# 01_commref_config.net
KiCad netlist of a schematic drawn in Altium Designer
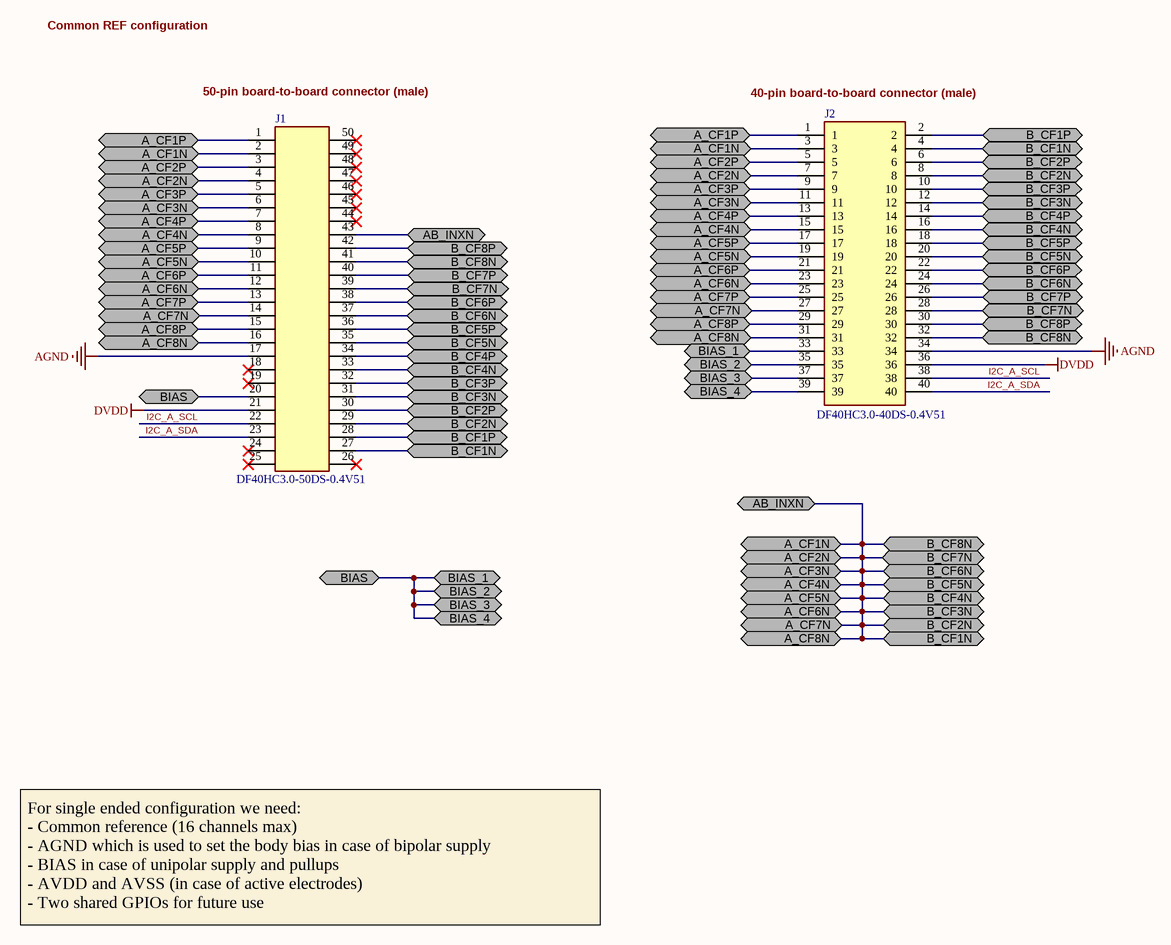
[diagram p0: 01_commref_config.SchDoc]

(export (version "E")
  (design (tool "Eeschema 10.0.6"))
  (components
    (comp (ref "J1")
      (value "DF40HC3.0-50DS-0.4V51")
      (footprint "CONN_DF40HC3.0-50DS-0.4V51_HIR")
      (description "No Description Available")
      (libsource (lib "DF40HC3P0-50DS-0P4V51") (part "DF40HC3.0-50DS-0.4V51"))
    )
    (comp (ref "J2")
      (value "DF40HC3.0-40DS-0.4V51")
      (footprint "CONN40_DF40HC-40DS_HIR")
      (description "No Description Available")
      (libsource (lib "DF40HC3P0-40DS-0P4V51") (part "DF40HC3.0-40DS-0.4V51"))
    )
  )
  (nets
    (net (code "1") (name "/AB_INXN") (class "Default")
      (node (ref "J1") (pin "10") (pintype "passive"))
      (node (ref "J1") (pin "12") (pintype "passive"))
      (node (ref "J1") (pin "14") (pintype "passive"))
      (node (ref "J1") (pin "16") (pintype "passive"))
      (node (ref "J1") (pin "2") (pintype "passive"))
      (node (ref "J1") (pin "27") (pintype "passive"))
      (node (ref "J1") (pin "29") (pintype "passive"))
      (node (ref "J1") (pin "31") (pintype "passive"))
      (node (ref "J1") (pin "33") (pintype "passive"))
      (node (ref "J1") (pin "35") (pintype "passive"))
      (node (ref "J1") (pin "37") (pintype "passive"))
      (node (ref "J1") (pin "39") (pintype "passive"))
      (node (ref "J1") (pin "4") (pintype "passive"))
      (node (ref "J1") (pin "41") (pintype "passive"))
      (node (ref "J1") (pin "43") (pintype "passive"))
      (node (ref "J1") (pin "6") (pintype "passive"))
      (node (ref "J1") (pin "8") (pintype "passive"))
      (node (ref "J2") (pin "11") (pinfunction "11_11") (pintype "passive"))
      (node (ref "J2") (pin "12") (pinfunction "12_12") (pintype "passive"))
      (node (ref "J2") (pin "15") (pinfunction "15_15") (pintype "passive"))
      (node (ref "J2") (pin "16") (pinfunction "16_16") (pintype "passive"))
      (node (ref "J2") (pin "19") (pinfunction "19_19") (pintype "passive"))
      (node (ref "J2") (pin "20") (pinfunction "20_20") (pintype "passive"))
      (node (ref "J2") (pin "23") (pinfunction "23_23") (pintype "passive"))
      (node (ref "J2") (pin "24") (pinfunction "24_24") (pintype "passive"))
      (node (ref "J2") (pin "27") (pinfunction "27_27") (pintype "passive"))
      (node (ref "J2") (pin "28") (pinfunction "28_28") (pintype "passive"))
      (node (ref "J2") (pin "3") (pinfunction "3_3") (pintype "passive"))
      (node (ref "J2") (pin "31") (pinfunction "31_31") (pintype "passive"))
      (node (ref "J2") (pin "32") (pinfunction "32_32") (pintype "passive"))
      (node (ref "J2") (pin "4") (pinfunction "4_4") (pintype "passive"))
      (node (ref "J2") (pin "7") (pinfunction "7_7") (pintype "passive"))
      (node (ref "J2") (pin "8") (pinfunction "8_8") (pintype "passive"))
    )
    (net (code "2") (name "/A_CF1P") (class "Default")
      (node (ref "J1") (pin "1") (pintype "passive"))
      (node (ref "J2") (pin "1") (pinfunction "1_1") (pintype "passive"))
    )
    (net (code "3") (name "/A_CF2P") (class "Default")
      (node (ref "J1") (pin "3") (pintype "passive"))
      (node (ref "J2") (pin "5") (pinfunction "5_5") (pintype "passive"))
    )
    (net (code "4") (name "/A_CF3P") (class "Default")
      (node (ref "J1") (pin "5") (pintype "passive"))
      (node (ref "J2") (pin "9") (pinfunction "9_9") (pintype "passive"))
    )
    (net (code "5") (name "/A_CF4P") (class "Default")
      (node (ref "J1") (pin "7") (pintype "passive"))
      (node (ref "J2") (pin "13") (pinfunction "13_13") (pintype "passive"))
    )
    (net (code "6") (name "/A_CF5P") (class "Default")
      (node (ref "J1") (pin "9") (pintype "passive"))
      (node (ref "J2") (pin "17") (pinfunction "17_17") (pintype "passive"))
    )
    (net (code "7") (name "/A_CF6P") (class "Default")
      (node (ref "J1") (pin "11") (pintype "passive"))
      (node (ref "J2") (pin "21") (pinfunction "21_21") (pintype "passive"))
    )
    (net (code "8") (name "/A_CF7P") (class "Default")
      (node (ref "J1") (pin "13") (pintype "passive"))
      (node (ref "J2") (pin "25") (pinfunction "25_25") (pintype "passive"))
    )
    (net (code "9") (name "/A_CF8P") (class "Default")
      (node (ref "J1") (pin "15") (pintype "passive"))
      (node (ref "J2") (pin "29") (pinfunction "29_29") (pintype "passive"))
    )
    (net (code "10") (name "/BIAS") (class "Default")
      (node (ref "J1") (pin "20") (pintype "passive"))
      (node (ref "J2") (pin "33") (pinfunction "33_33") (pintype "passive"))
      (node (ref "J2") (pin "35") (pinfunction "35_35") (pintype "passive"))
      (node (ref "J2") (pin "37") (pinfunction "37_37") (pintype "passive"))
      (node (ref "J2") (pin "39") (pinfunction "39_39") (pintype "passive"))
    )
    (net (code "11") (name "/B_CF1P") (class "Default")
      (node (ref "J1") (pin "28") (pintype "passive"))
      (node (ref "J2") (pin "2") (pinfunction "2_2") (pintype "passive"))
    )
    (net (code "12") (name "/B_CF2P") (class "Default")
      (node (ref "J1") (pin "30") (pintype "passive"))
      (node (ref "J2") (pin "6") (pinfunction "6_6") (pintype "passive"))
    )
    (net (code "13") (name "/B_CF3P") (class "Default")
      (node (ref "J1") (pin "32") (pintype "passive"))
      (node (ref "J2") (pin "10") (pinfunction "10_10") (pintype "passive"))
    )
    (net (code "14") (name "/B_CF4P") (class "Default")
      (node (ref "J1") (pin "34") (pintype "passive"))
      (node (ref "J2") (pin "14") (pinfunction "14_14") (pintype "passive"))
    )
    (net (code "15") (name "/B_CF5P") (class "Default")
      (node (ref "J1") (pin "36") (pintype "passive"))
      (node (ref "J2") (pin "18") (pinfunction "18_18") (pintype "passive"))
    )
    (net (code "16") (name "/B_CF6P") (class "Default")
      (node (ref "J1") (pin "38") (pintype "passive"))
      (node (ref "J2") (pin "22") (pinfunction "22_22") (pintype "passive"))
    )
    (net (code "17") (name "/B_CF7P") (class "Default")
      (node (ref "J1") (pin "40") (pintype "passive"))
      (node (ref "J2") (pin "26") (pinfunction "26_26") (pintype "passive"))
    )
    (net (code "18") (name "/B_CF8P") (class "Default")
      (node (ref "J1") (pin "42") (pintype "passive"))
      (node (ref "J2") (pin "30") (pinfunction "30_30") (pintype "passive"))
    )
    (net (code "19") (name "/I2C_A_SCL") (class "Default")
      (node (ref "J1") (pin "22") (pintype "passive"))
      (node (ref "J2") (pin "38") (pinfunction "38_38") (pintype "passive"))
    )
    (net (code "20") (name "/I2C_A_SDA") (class "Default")
      (node (ref "J1") (pin "23") (pintype "passive"))
      (node (ref "J2") (pin "40") (pinfunction "40_40") (pintype "passive"))
    )
    (net (code "21") (name "AGND") (class "Default")
      (node (ref "J1") (pin "17") (pintype "passive"))
      (node (ref "J2") (pin "34") (pinfunction "34_34") (pintype "passive"))
    )
    (net (code "22") (name "DVDD") (class "Default")
      (node (ref "J1") (pin "21") (pintype "passive"))
      (node (ref "J2") (pin "36") (pinfunction "36_36") (pintype "passive"))
    )
    (net (code "23") (name "unconnected-(J1-Pad18)") (class "Default")
      (node (ref "J1") (pin "18") (pintype "passive+no_connect"))
    )
    (net (code "24") (name "unconnected-(J1-Pad19)") (class "Default")
      (node (ref "J1") (pin "19") (pintype "passive+no_connect"))
    )
    (net (code "25") (name "unconnected-(J1-Pad24)") (class "Default")
      (node (ref "J1") (pin "24") (pintype "passive+no_connect"))
    )
    (net (code "26") (name "unconnected-(J1-Pad25)") (class "Default")
      (node (ref "J1") (pin "25") (pintype "passive+no_connect"))
    )
    (net (code "27") (name "unconnected-(J1-Pad26)") (class "Default")
      (node (ref "J1") (pin "26") (pintype "passive+no_connect"))
    )
    (net (code "28") (name "unconnected-(J1-Pad44)") (class "Default")
      (node (ref "J1") (pin "44") (pintype "passive+no_connect"))
    )
    (net (code "29") (name "unconnected-(J1-Pad45)") (class "Default")
      (node (ref "J1") (pin "45") (pintype "passive+no_connect"))
    )
    (net (code "30") (name "unconnected-(J1-Pad46)") (class "Default")
      (node (ref "J1") (pin "46") (pintype "passive+no_connect"))
    )
    (net (code "31") (name "unconnected-(J1-Pad47)") (class "Default")
      (node (ref "J1") (pin "47") (pintype "passive+no_connect"))
    )
    (net (code "32") (name "unconnected-(J1-Pad48)") (class "Default")
      (node (ref "J1") (pin "48") (pintype "passive+no_connect"))
    )
    (net (code "33") (name "unconnected-(J1-Pad49)") (class "Default")
      (node (ref "J1") (pin "49") (pintype "passive+no_connect"))
    )
    (net (code "34") (name "unconnected-(J1-Pad50)") (class "Default")
      (node (ref "J1") (pin "50") (pintype "passive+no_connect"))
    )
  )
)
